# DAQ.net
KiCad netlist of a schematic drawn in Altium Designer
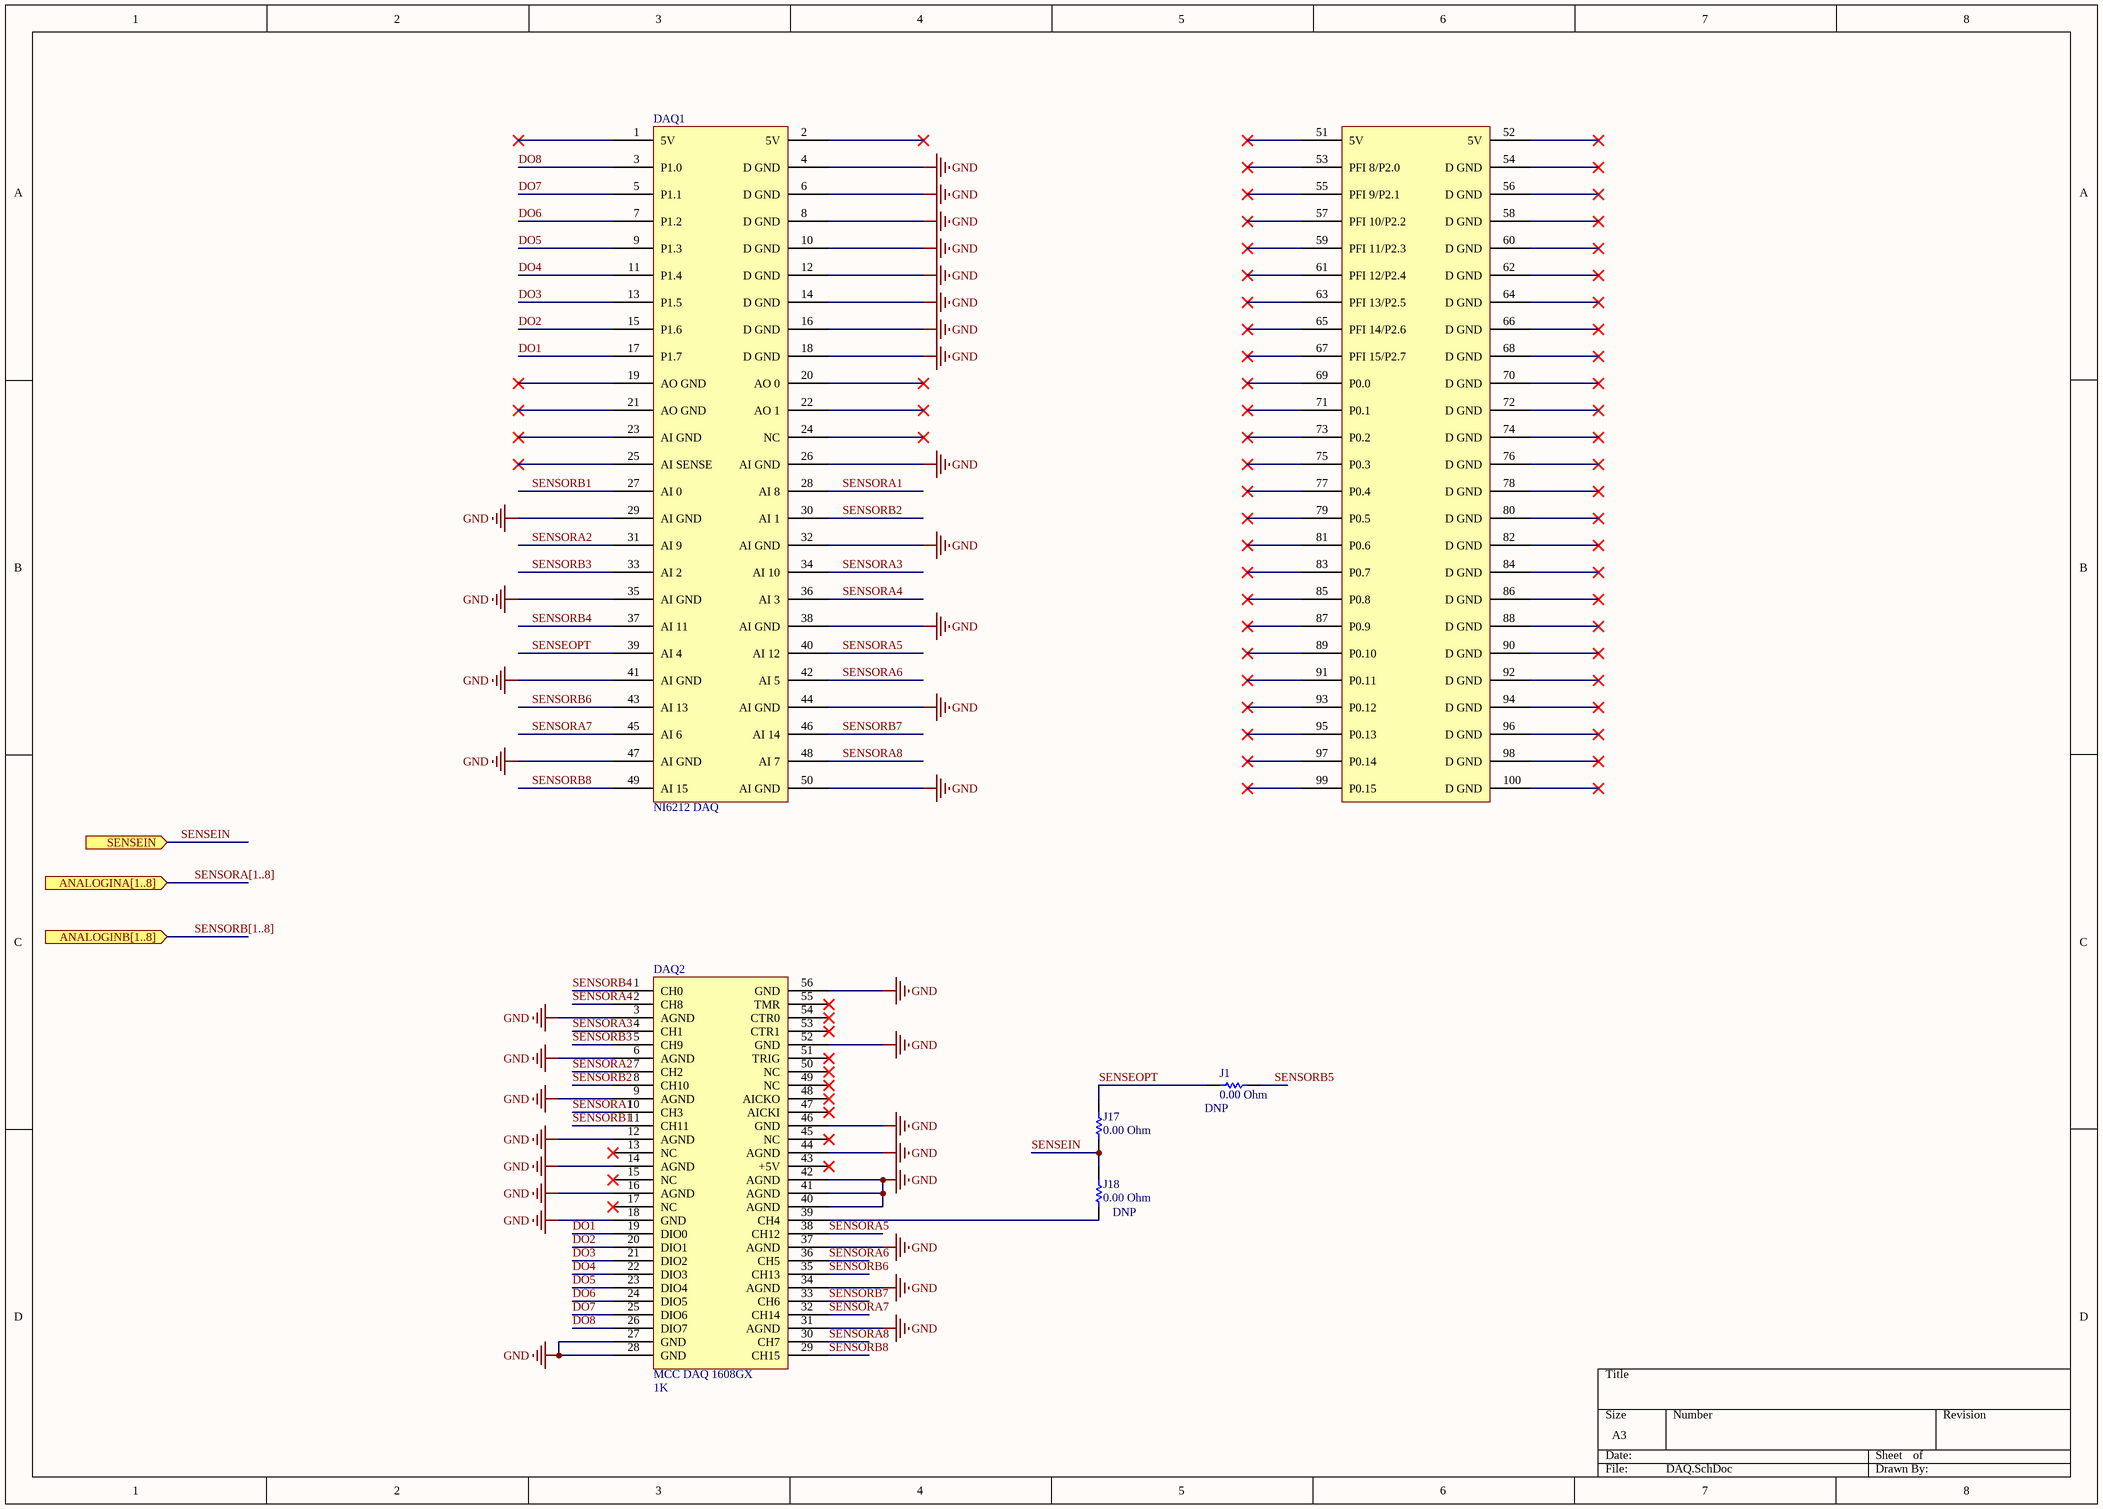
[diagram p0: DAQ.SchDoc]

(export (version "E")
  (design (tool "Eeschema 10.0.6"))
  (components
    (comp (ref "DAQ1")
      (value "NI6212 DAQ")
      (footprint "NIDAQ6212")
      (description "DAQ Unit")
      (fields (field (name "PUBLISHER") "National Instruments"))
      (libsource (lib "NI6212") (part "NI6212"))
    )
    (comp (ref "DAQ2")
      (value "MCC DAQ 1608GX")
      (footprint "DAQ_MCC")
      (description "MCC USB-1608GX_OEM")
      (fields (field (name "ALTIUM_VALUE") "1K") (field (name "PUBLISHER") "Altium Limited"))
      (libsource (lib "AnserEMT") (part "MCC USB-1608GX_OEM"))
    )
    (comp (ref "J1")
      (value "0.00 Ohm")
      (footprint "RESC1206(3216)_M")
      (description "Jumper 1206 (3216 Metric)")
      (fields (field (name "TOLERANCE") "None") (field (name "OPTION") "DNP"))
      (libsource (lib "Altium Content Vault") (part "CMP-1014-00001-1"))
    )
    (comp (ref "J17")
      (value "0.00 Ohm")
      (footprint "RESC1206(3216)_M")
      (description "Jumper 1206 (3216 Metric)")
      (fields (field (name "TOLERANCE") "None"))
      (libsource (lib "Altium Content Vault") (part "CMP-1014-00001-1"))
    )
    (comp (ref "J18")
      (value "0.00 Ohm")
      (footprint "RESC1206(3216)_M")
      (description "Jumper 1206 (3216 Metric)")
      (fields (field (name "TOLERANCE") "None") (field (name "OPTION") "DNP"))
      (libsource (lib "Altium Content Vault") (part "CMP-1014-00001-1"))
    )
  )
  (nets
    (net (code "1") (name "/DO1") (class "Default")
      (node (ref "DAQ1") (pin "17") (pinfunction "P1.7_17") (pintype "passive"))
      (node (ref "DAQ2") (pin "19") (pinfunction "DIO0_19") (pintype "passive"))
    )
    (net (code "2") (name "/DO2") (class "Default")
      (node (ref "DAQ1") (pin "15") (pinfunction "P1.6_15") (pintype "passive"))
      (node (ref "DAQ2") (pin "20") (pinfunction "DIO1_20") (pintype "passive"))
    )
    (net (code "3") (name "/DO3") (class "Default")
      (node (ref "DAQ1") (pin "13") (pinfunction "P1.5_13") (pintype "passive"))
      (node (ref "DAQ2") (pin "21") (pinfunction "DIO2_21") (pintype "passive"))
    )
    (net (code "4") (name "/DO4") (class "Default")
      (node (ref "DAQ1") (pin "11") (pinfunction "P1.4_11") (pintype "passive"))
      (node (ref "DAQ2") (pin "22") (pinfunction "DIO3_22") (pintype "passive"))
    )
    (net (code "5") (name "/DO5") (class "Default")
      (node (ref "DAQ1") (pin "9") (pinfunction "P1.3_9") (pintype "passive"))
      (node (ref "DAQ2") (pin "23") (pinfunction "DIO4_23") (pintype "passive"))
    )
    (net (code "6") (name "/DO6") (class "Default")
      (node (ref "DAQ1") (pin "7") (pinfunction "P1.2_7") (pintype "passive"))
      (node (ref "DAQ2") (pin "24") (pinfunction "DIO5_24") (pintype "passive"))
    )
    (net (code "7") (name "/DO7") (class "Default")
      (node (ref "DAQ1") (pin "5") (pinfunction "P1.1_5") (pintype "passive"))
      (node (ref "DAQ2") (pin "25") (pinfunction "DIO6_25") (pintype "passive"))
    )
    (net (code "8") (name "/DO8") (class "Default")
      (node (ref "DAQ1") (pin "3") (pinfunction "P1.0_3") (pintype "passive"))
      (node (ref "DAQ2") (pin "26") (pinfunction "DIO7_26") (pintype "passive"))
    )
    (net (code "9") (name "/SENSEIN") (class "Default")
      (node (ref "J17") (pin "1") (pinfunction "1_1") (pintype "passive"))
      (node (ref "J18") (pin "2") (pinfunction "2_2") (pintype "passive"))
    )
    (net (code "10") (name "/SENSEOPT") (class "Default")
      (node (ref "DAQ1") (pin "39") (pinfunction "AI_4_39") (pintype "passive"))
      (node (ref "J1") (pin "2") (pinfunction "2_2") (pintype "passive"))
      (node (ref "J17") (pin "2") (pinfunction "2_2") (pintype "passive"))
    )
    (net (code "11") (name "/SENSORA1") (class "Default")
      (node (ref "DAQ1") (pin "28") (pinfunction "AI_8_28") (pintype "passive"))
      (node (ref "DAQ2") (pin "10") (pinfunction "CH3_10") (pintype "passive"))
    )
    (net (code "12") (name "/SENSORA2") (class "Default")
      (node (ref "DAQ1") (pin "31") (pinfunction "AI_9_31") (pintype "passive"))
      (node (ref "DAQ2") (pin "7") (pinfunction "CH2_7") (pintype "passive"))
    )
    (net (code "13") (name "/SENSORA3") (class "Default")
      (node (ref "DAQ1") (pin "34") (pinfunction "AI_10_34") (pintype "passive"))
      (node (ref "DAQ2") (pin "4") (pinfunction "CH1_4") (pintype "passive"))
    )
    (net (code "14") (name "/SENSORA4") (class "Default")
      (node (ref "DAQ1") (pin "36") (pinfunction "AI_3_36") (pintype "passive"))
      (node (ref "DAQ2") (pin "2") (pinfunction "CH8_2") (pintype "passive"))
    )
    (net (code "15") (name "/SENSORA5") (class "Default")
      (node (ref "DAQ1") (pin "40") (pinfunction "AI_12_40") (pintype "passive"))
      (node (ref "DAQ2") (pin "38") (pinfunction "CH12_38") (pintype "passive"))
    )
    (net (code "16") (name "/SENSORA6") (class "Default")
      (node (ref "DAQ1") (pin "42") (pinfunction "AI_5_42") (pintype "passive"))
      (node (ref "DAQ2") (pin "36") (pinfunction "CH5_36") (pintype "passive"))
    )
    (net (code "17") (name "/SENSORA7") (class "Default")
      (node (ref "DAQ1") (pin "45") (pinfunction "AI_6_45") (pintype "passive"))
      (node (ref "DAQ2") (pin "32") (pinfunction "CH14_32") (pintype "passive"))
    )
    (net (code "18") (name "/SENSORA8") (class "Default")
      (node (ref "DAQ1") (pin "48") (pinfunction "AI_7_48") (pintype "passive"))
      (node (ref "DAQ2") (pin "30") (pinfunction "CH7_30") (pintype "passive"))
    )
    (net (code "20") (name "/SENSORB1") (class "Default")
      (node (ref "DAQ1") (pin "27") (pinfunction "AI_0_27") (pintype "passive"))
      (node (ref "DAQ2") (pin "11") (pinfunction "CH11_11") (pintype "passive"))
    )
    (net (code "21") (name "/SENSORB2") (class "Default")
      (node (ref "DAQ1") (pin "30") (pinfunction "AI_1_30") (pintype "passive"))
      (node (ref "DAQ2") (pin "8") (pinfunction "CH10_8") (pintype "passive"))
    )
    (net (code "22") (name "/SENSORB3") (class "Default")
      (node (ref "DAQ1") (pin "33") (pinfunction "AI_2_33") (pintype "passive"))
      (node (ref "DAQ2") (pin "5") (pinfunction "CH9_5") (pintype "passive"))
    )
    (net (code "23") (name "/SENSORB4") (class "Default")
      (node (ref "DAQ1") (pin "37") (pinfunction "AI_11_37") (pintype "passive"))
      (node (ref "DAQ2") (pin "1") (pinfunction "CH0_1") (pintype "passive"))
    )
    (net (code "24") (name "/SENSORB5") (class "Default")
      (node (ref "J1") (pin "1") (pinfunction "1_1") (pintype "passive"))
    )
    (net (code "25") (name "/SENSORB6") (class "Default")
      (node (ref "DAQ1") (pin "43") (pinfunction "AI_13_43") (pintype "passive"))
      (node (ref "DAQ2") (pin "35") (pinfunction "CH13_35") (pintype "passive"))
    )
    (net (code "26") (name "/SENSORB7") (class "Default")
      (node (ref "DAQ1") (pin "46") (pinfunction "AI_14_46") (pintype "passive"))
      (node (ref "DAQ2") (pin "33") (pinfunction "CH6_33") (pintype "passive"))
    )
    (net (code "27") (name "/SENSORB8") (class "Default")
      (node (ref "DAQ1") (pin "49") (pinfunction "AI_15_49") (pintype "passive"))
      (node (ref "DAQ2") (pin "29") (pinfunction "CH15_29") (pintype "passive"))
    )
    (net (code "29") (name "GND") (class "Default")
      (node (ref "DAQ1") (pin "10") (pinfunction "D_GND_10") (pintype "passive"))
      (node (ref "DAQ1") (pin "12") (pinfunction "D_GND_12") (pintype "passive"))
      (node (ref "DAQ1") (pin "14") (pinfunction "D_GND_14") (pintype "passive"))
      (node (ref "DAQ1") (pin "16") (pinfunction "D_GND_16") (pintype "passive"))
      (node (ref "DAQ1") (pin "18") (pinfunction "D_GND_18") (pintype "passive"))
      (node (ref "DAQ1") (pin "26") (pinfunction "AI_GND_26") (pintype "passive"))
      (node (ref "DAQ1") (pin "29") (pinfunction "AI_GND_29") (pintype "passive"))
      (node (ref "DAQ1") (pin "32") (pinfunction "AI_GND_32") (pintype "passive"))
      (node (ref "DAQ1") (pin "35") (pinfunction "AI_GND_35") (pintype "passive"))
      (node (ref "DAQ1") (pin "38") (pinfunction "AI_GND_38") (pintype "passive"))
      (node (ref "DAQ1") (pin "4") (pinfunction "D_GND_4") (pintype "passive"))
      (node (ref "DAQ1") (pin "41") (pinfunction "AI_GND_41") (pintype "passive"))
      (node (ref "DAQ1") (pin "44") (pinfunction "AI_GND_44") (pintype "passive"))
      (node (ref "DAQ1") (pin "47") (pinfunction "AI_GND_47") (pintype "passive"))
      (node (ref "DAQ1") (pin "50") (pinfunction "AI_GND_50") (pintype "passive"))
      (node (ref "DAQ1") (pin "6") (pinfunction "D_GND_6") (pintype "passive"))
      (node (ref "DAQ1") (pin "8") (pinfunction "D_GND_8") (pintype "passive"))
      (node (ref "DAQ2") (pin "12") (pinfunction "AGND_12") (pintype "passive"))
      (node (ref "DAQ2") (pin "14") (pinfunction "AGND_14") (pintype "passive"))
      (node (ref "DAQ2") (pin "16") (pinfunction "AGND_16") (pintype "passive"))
      (node (ref "DAQ2") (pin "18") (pinfunction "GND_18") (pintype "passive"))
      (node (ref "DAQ2") (pin "27") (pinfunction "GND_27") (pintype "passive"))
      (node (ref "DAQ2") (pin "28") (pinfunction "GND_28") (pintype "passive"))
      (node (ref "DAQ2") (pin "3") (pinfunction "AGND_3") (pintype "passive"))
      (node (ref "DAQ2") (pin "31") (pinfunction "AGND_31") (pintype "passive"))
      (node (ref "DAQ2") (pin "34") (pinfunction "AGND_34") (pintype "passive"))
      (node (ref "DAQ2") (pin "37") (pinfunction "AGND_37") (pintype "passive"))
      (node (ref "DAQ2") (pin "40") (pinfunction "AGND_40") (pintype "passive"))
      (node (ref "DAQ2") (pin "41") (pinfunction "AGND_41") (pintype "passive"))
      (node (ref "DAQ2") (pin "42") (pinfunction "AGND_42") (pintype "passive"))
      (node (ref "DAQ2") (pin "44") (pinfunction "AGND_44") (pintype "passive"))
      (node (ref "DAQ2") (pin "46") (pinfunction "GND_46") (pintype "passive"))
      (node (ref "DAQ2") (pin "52") (pinfunction "GND_52") (pintype "passive"))
      (node (ref "DAQ2") (pin "56") (pinfunction "GND_56") (pintype "passive"))
      (node (ref "DAQ2") (pin "6") (pinfunction "AGND_6") (pintype "passive"))
      (node (ref "DAQ2") (pin "9") (pinfunction "AGND_9") (pintype "passive"))
    )
    (net (code "30") (name "Net-(DAQ2-CH4)") (class "Default")
      (node (ref "DAQ2") (pin "39") (pinfunction "CH4_39") (pintype "passive"))
      (node (ref "J18") (pin "1") (pinfunction "1_1") (pintype "passive"))
    )
    (net (code "31") (name "unconnected-(DAQ1-5V-Pad1)") (class "Default")
      (node (ref "DAQ1") (pin "1") (pinfunction "5V_1") (pintype "passive+no_connect"))
    )
    (net (code "32") (name "unconnected-(DAQ1-5V-Pad2)") (class "Default")
      (node (ref "DAQ1") (pin "2") (pinfunction "5V_2") (pintype "passive+no_connect"))
    )
    (net (code "33") (name "unconnected-(DAQ1-5V-Pad51)") (class "Default")
      (node (ref "DAQ1") (pin "51") (pinfunction "5V_51") (pintype "passive+no_connect"))
    )
    (net (code "34") (name "unconnected-(DAQ1-5V-Pad52)") (class "Default")
      (node (ref "DAQ1") (pin "52") (pinfunction "5V_52") (pintype "passive+no_connect"))
    )
    (net (code "35") (name "unconnected-(DAQ1-AI_GND-Pad23)") (class "Default")
      (node (ref "DAQ1") (pin "23") (pinfunction "AI_GND_23") (pintype "passive+no_connect"))
    )
    (net (code "36") (name "unconnected-(DAQ1-AI_SENSE-Pad25)") (class "Default")
      (node (ref "DAQ1") (pin "25") (pinfunction "AI_SENSE_25") (pintype "passive+no_connect"))
    )
    (net (code "37") (name "unconnected-(DAQ1-AO_0-Pad20)") (class "Default")
      (node (ref "DAQ1") (pin "20") (pinfunction "AO_0_20") (pintype "passive+no_connect"))
    )
    (net (code "38") (name "unconnected-(DAQ1-AO_1-Pad22)") (class "Default")
      (node (ref "DAQ1") (pin "22") (pinfunction "AO_1_22") (pintype "passive+no_connect"))
    )
    (net (code "39") (name "unconnected-(DAQ1-AO_GND-Pad19)") (class "Default")
      (node (ref "DAQ1") (pin "19") (pinfunction "AO_GND_19") (pintype "passive+no_connect"))
    )
    (net (code "40") (name "unconnected-(DAQ1-AO_GND-Pad21)") (class "Default")
      (node (ref "DAQ1") (pin "21") (pinfunction "AO_GND_21") (pintype "passive+no_connect"))
    )
    (net (code "41") (name "unconnected-(DAQ1-D_GND-Pad54)") (class "Default")
      (node (ref "DAQ1") (pin "54") (pinfunction "D_GND_54") (pintype "passive+no_connect"))
    )
    (net (code "42") (name "unconnected-(DAQ1-D_GND-Pad56)") (class "Default")
      (node (ref "DAQ1") (pin "56") (pinfunction "D_GND_56") (pintype "passive+no_connect"))
    )
    (net (code "43") (name "unconnected-(DAQ1-D_GND-Pad58)") (class "Default")
      (node (ref "DAQ1") (pin "58") (pinfunction "D_GND_58") (pintype "passive+no_connect"))
    )
    (net (code "44") (name "unconnected-(DAQ1-D_GND-Pad60)") (class "Default")
      (node (ref "DAQ1") (pin "60") (pinfunction "D_GND_60") (pintype "passive+no_connect"))
    )
    (net (code "45") (name "unconnected-(DAQ1-D_GND-Pad62)") (class "Default")
      (node (ref "DAQ1") (pin "62") (pinfunction "D_GND_62") (pintype "passive+no_connect"))
    )
    (net (code "46") (name "unconnected-(DAQ1-D_GND-Pad64)") (class "Default")
      (node (ref "DAQ1") (pin "64") (pinfunction "D_GND_64") (pintype "passive+no_connect"))
    )
    (net (code "47") (name "unconnected-(DAQ1-D_GND-Pad66)") (class "Default")
      (node (ref "DAQ1") (pin "66") (pinfunction "D_GND_66") (pintype "passive+no_connect"))
    )
    (net (code "48") (name "unconnected-(DAQ1-D_GND-Pad68)") (class "Default")
      (node (ref "DAQ1") (pin "68") (pinfunction "D_GND_68") (pintype "passive+no_connect"))
    )
    (net (code "49") (name "unconnected-(DAQ1-D_GND-Pad70)") (class "Default")
      (node (ref "DAQ1") (pin "70") (pinfunction "D_GND_70") (pintype "passive+no_connect"))
    )
    (net (code "50") (name "unconnected-(DAQ1-D_GND-Pad72)") (class "Default")
      (node (ref "DAQ1") (pin "72") (pinfunction "D_GND_72") (pintype "passive+no_connect"))
    )
    (net (code "51") (name "unconnected-(DAQ1-D_GND-Pad74)") (class "Default")
      (node (ref "DAQ1") (pin "74") (pinfunction "D_GND_74") (pintype "passive+no_connect"))
    )
    (net (code "52") (name "unconnected-(DAQ1-D_GND-Pad76)") (class "Default")
      (node (ref "DAQ1") (pin "76") (pinfunction "D_GND_76") (pintype "passive+no_connect"))
    )
    (net (code "53") (name "unconnected-(DAQ1-D_GND-Pad78)") (class "Default")
      (node (ref "DAQ1") (pin "78") (pinfunction "D_GND_78") (pintype "passive+no_connect"))
    )
    (net (code "54") (name "unconnected-(DAQ1-D_GND-Pad80)") (class "Default")
      (node (ref "DAQ1") (pin "80") (pinfunction "D_GND_80") (pintype "passive+no_connect"))
    )
    (net (code "55") (name "unconnected-(DAQ1-D_GND-Pad82)") (class "Default")
      (node (ref "DAQ1") (pin "82") (pinfunction "D_GND_82") (pintype "passive+no_connect"))
    )
    (net (code "56") (name "unconnected-(DAQ1-D_GND-Pad84)") (class "Default")
      (node (ref "DAQ1") (pin "84") (pinfunction "D_GND_84") (pintype "passive+no_connect"))
    )
    (net (code "57") (name "unconnected-(DAQ1-D_GND-Pad86)") (class "Default")
      (node (ref "DAQ1") (pin "86") (pinfunction "D_GND_86") (pintype "passive+no_connect"))
    )
    (net (code "58") (name "unconnected-(DAQ1-D_GND-Pad88)") (class "Default")
      (node (ref "DAQ1") (pin "88") (pinfunction "D_GND_88") (pintype "passive+no_connect"))
    )
    (net (code "59") (name "unconnected-(DAQ1-D_GND-Pad90)") (class "Default")
      (node (ref "DAQ1") (pin "90") (pinfunction "D_GND_90") (pintype "passive+no_connect"))
    )
    (net (code "60") (name "unconnected-(DAQ1-D_GND-Pad92)") (class "Default")
      (node (ref "DAQ1") (pin "92") (pinfunction "D_GND_92") (pintype "passive+no_connect"))
    )
    (net (code "61") (name "unconnected-(DAQ1-D_GND-Pad94)") (class "Default")
      (node (ref "DAQ1") (pin "94") (pinfunction "D_GND_94") (pintype "passive+no_connect"))
    )
    (net (code "62") (name "unconnected-(DAQ1-D_GND-Pad96)") (class "Default")
      (node (ref "DAQ1") (pin "96") (pinfunction "D_GND_96") (pintype "passive+no_connect"))
    )
    (net (code "63") (name "unconnected-(DAQ1-D_GND-Pad98)") (class "Default")
      (node (ref "DAQ1") (pin "98") (pinfunction "D_GND_98") (pintype "passive+no_connect"))
    )
    (net (code "64") (name "unconnected-(DAQ1-D_GND-Pad100)") (class "Default")
      (node (ref "DAQ1") (pin "100") (pinfunction "D_GND_100") (pintype "passive+no_connect"))
    )
    (net (code "65") (name "unconnected-(DAQ1-NC-Pad24)") (class "Default")
      (node (ref "DAQ1") (pin "24") (pinfunction "NC_24") (pintype "passive+no_connect"))
    )
    (net (code "66") (name "unconnected-(DAQ1-P0.0-Pad69)") (class "Default")
      (node (ref "DAQ1") (pin "69") (pinfunction "P0.0_69") (pintype "passive+no_connect"))
    )
    (net (code "67") (name "unconnected-(DAQ1-P0.1-Pad71)") (class "Default")
      (node (ref "DAQ1") (pin "71") (pinfunction "P0.1_71") (pintype "passive+no_connect"))
    )
    (net (code "68") (name "unconnected-(DAQ1-P0.2-Pad73)") (class "Default")
      (node (ref "DAQ1") (pin "73") (pinfunction "P0.2_73") (pintype "passive+no_connect"))
    )
    (net (code "69") (name "unconnected-(DAQ1-P0.3-Pad75)") (class "Default")
      (node (ref "DAQ1") (pin "75") (pinfunction "P0.3_75") (pintype "passive+no_connect"))
    )
    (net (code "70") (name "unconnected-(DAQ1-P0.4-Pad77)") (class "Default")
      (node (ref "DAQ1") (pin "77") (pinfunction "P0.4_77") (pintype "passive+no_connect"))
    )
    (net (code "71") (name "unconnected-(DAQ1-P0.5-Pad79)") (class "Default")
      (node (ref "DAQ1") (pin "79") (pinfunction "P0.5_79") (pintype "passive+no_connect"))
    )
    (net (code "72") (name "unconnected-(DAQ1-P0.6-Pad81)") (class "Default")
      (node (ref "DAQ1") (pin "81") (pinfunction "P0.6_81") (pintype "passive+no_connect"))
    )
    (net (code "73") (name "unconnected-(DAQ1-P0.7-Pad83)") (class "Default")
      (node (ref "DAQ1") (pin "83") (pinfunction "P0.7_83") (pintype "passive+no_connect"))
    )
    (net (code "74") (name "unconnected-(DAQ1-P0.8-Pad85)") (class "Default")
      (node (ref "DAQ1") (pin "85") (pinfunction "P0.8_85") (pintype "passive+no_connect"))
    )
    (net (code "75") (name "unconnected-(DAQ1-P0.9-Pad87)") (class "Default")
      (node (ref "DAQ1") (pin "87") (pinfunction "P0.9_87") (pintype "passive+no_connect"))
    )
    (net (code "76") (name "unconnected-(DAQ1-P0.10-Pad89)") (class "Default")
      (node (ref "DAQ1") (pin "89") (pinfunction "P0.10_89") (pintype "passive+no_connect"))
    )
    (net (code "77") (name "unconnected-(DAQ1-P0.11-Pad91)") (class "Default")
      (node (ref "DAQ1") (pin "91") (pinfunction "P0.11_91") (pintype "passive+no_connect"))
    )
    (net (code "78") (name "unconnected-(DAQ1-P0.12-Pad93)") (class "Default")
      (node (ref "DAQ1") (pin "93") (pinfunction "P0.12_93") (pintype "passive+no_connect"))
    )
    (net (code "79") (name "unconnected-(DAQ1-P0.13-Pad95)") (class "Default")
      (node (ref "DAQ1") (pin "95") (pinfunction "P0.13_95") (pintype "passive+no_connect"))
    )
    (net (code "80") (name "unconnected-(DAQ1-P0.14-Pad97)") (class "Default")
      (node (ref "DAQ1") (pin "97") (pinfunction "P0.14_97") (pintype "passive+no_connect"))
    )
    (net (code "81") (name "unconnected-(DAQ1-P0.15-Pad99)") (class "Default")
      (node (ref "DAQ1") (pin "99") (pinfunction "P0.15_99") (pintype "passive+no_connect"))
    )
    (net (code "82") (name "unconnected-(DAQ1-PFI_8{slash}P2.0-Pad53)") (class "Default")
      (node (ref "DAQ1") (pin "53") (pinfunction "PFI_8/P2.0_53") (pintype "passive+no_connect"))
    )
    (net (code "83") (name "unconnected-(DAQ1-PFI_9{slash}P2.1-Pad55)") (class "Default")
      (node (ref "DAQ1") (pin "55") (pinfunction "PFI_9/P2.1_55") (pintype "passive+no_connect"))
    )
    (net (code "84") (name "unconnected-(DAQ1-PFI_10{slash}P2.2-Pad57)") (class "Default")
      (node (ref "DAQ1") (pin "57") (pinfunction "PFI_10/P2.2_57") (pintype "passive+no_connect"))
    )
    (net (code "85") (name "unconnected-(DAQ1-PFI_11{slash}P2.3-Pad59)") (class "Default")
      (node (ref "DAQ1") (pin "59") (pinfunction "PFI_11/P2.3_59") (pintype "passive+no_connect"))
    )
    (net (code "86") (name "unconnected-(DAQ1-PFI_12{slash}P2.4-Pad61)") (class "Default")
      (node (ref "DAQ1") (pin "61") (pinfunction "PFI_12/P2.4_61") (pintype "passive+no_connect"))
    )
    (net (code "87") (name "unconnected-(DAQ1-PFI_13{slash}P2.5-Pad63)") (class "Default")
      (node (ref "DAQ1") (pin "63") (pinfunction "PFI_13/P2.5_63") (pintype "passive+no_connect"))
    )
    (net (code "88") (name "unconnected-(DAQ1-PFI_14{slash}P2.6-Pad65)") (class "Default")
      (node (ref "DAQ1") (pin "65") (pinfunction "PFI_14/P2.6_65") (pintype "passive+no_connect"))
    )
    (net (code "89") (name "unconnected-(DAQ1-PFI_15{slash}P2.7-Pad67)") (class "Default")
      (node (ref "DAQ1") (pin "67") (pinfunction "PFI_15/P2.7_67") (pintype "passive+no_connect"))
    )
    (net (code "90") (name "unconnected-(DAQ2-+5V-Pad43)") (class "Default")
      (node (ref "DAQ2") (pin "43") (pinfunction "+5V_43") (pintype "passive+no_connect"))
    )
    (net (code "91") (name "unconnected-(DAQ2-AICKI-Pad47)") (class "Default")
      (node (ref "DAQ2") (pin "47") (pinfunction "AICKI_47") (pintype "passive+no_connect"))
    )
    (net (code "92") (name "unconnected-(DAQ2-AICKO-Pad48)") (class "Default")
      (node (ref "DAQ2") (pin "48") (pinfunction "AICKO_48") (pintype "passive+no_connect"))
    )
    (net (code "93") (name "unconnected-(DAQ2-CTR0-Pad54)") (class "Default")
      (node (ref "DAQ2") (pin "54") (pinfunction "CTR0_54") (pintype "passive+no_connect"))
    )
    (net (code "94") (name "unconnected-(DAQ2-CTR1-Pad53)") (class "Default")
      (node (ref "DAQ2") (pin "53") (pinfunction "CTR1_53") (pintype "passive+no_connect"))
    )
    (net (code "95") (name "unconnected-(DAQ2-NC-Pad13)") (class "Default")
      (node (ref "DAQ2") (pin "13") (pinfunction "NC_13") (pintype "passive+no_connect"))
    )
    (net (code "96") (name "unconnected-(DAQ2-NC-Pad15)") (class "Default")
      (node (ref "DAQ2") (pin "15") (pinfunction "NC_15") (pintype "passive+no_connect"))
    )
    (net (code "97") (name "unconnected-(DAQ2-NC-Pad17)") (class "Default")
      (node (ref "DAQ2") (pin "17") (pinfunction "NC_17") (pintype "passive+no_connect"))
    )
    (net (code "98") (name "unconnected-(DAQ2-NC-Pad45)") (class "Default")
      (node (ref "DAQ2") (pin "45") (pinfunction "NC_45") (pintype "passive+no_connect"))
    )
    (net (code "99") (name "unconnected-(DAQ2-NC-Pad49)") (class "Default")
      (node (ref "DAQ2") (pin "49") (pinfunction "NC_49") (pintype "passive+no_connect"))
    )
    (net (code "100") (name "unconnected-(DAQ2-NC-Pad50)") (class "Default")
      (node (ref "DAQ2") (pin "50") (pinfunction "NC_50") (pintype "passive+no_connect"))
    )
    (net (code "101") (name "unconnected-(DAQ2-TMR-Pad55)") (class "Default")
      (node (ref "DAQ2") (pin "55") (pinfunction "TMR_55") (pintype "passive+no_connect"))
    )
    (net (code "102") (name "unconnected-(DAQ2-TRIG-Pad51)") (class "Default")
      (node (ref "DAQ2") (pin "51") (pinfunction "TRIG_51") (pintype "passive+no_connect"))
    )
  )
)
